# datalogger.net
KiCad netlist of a schematic drawn in Altium Designer
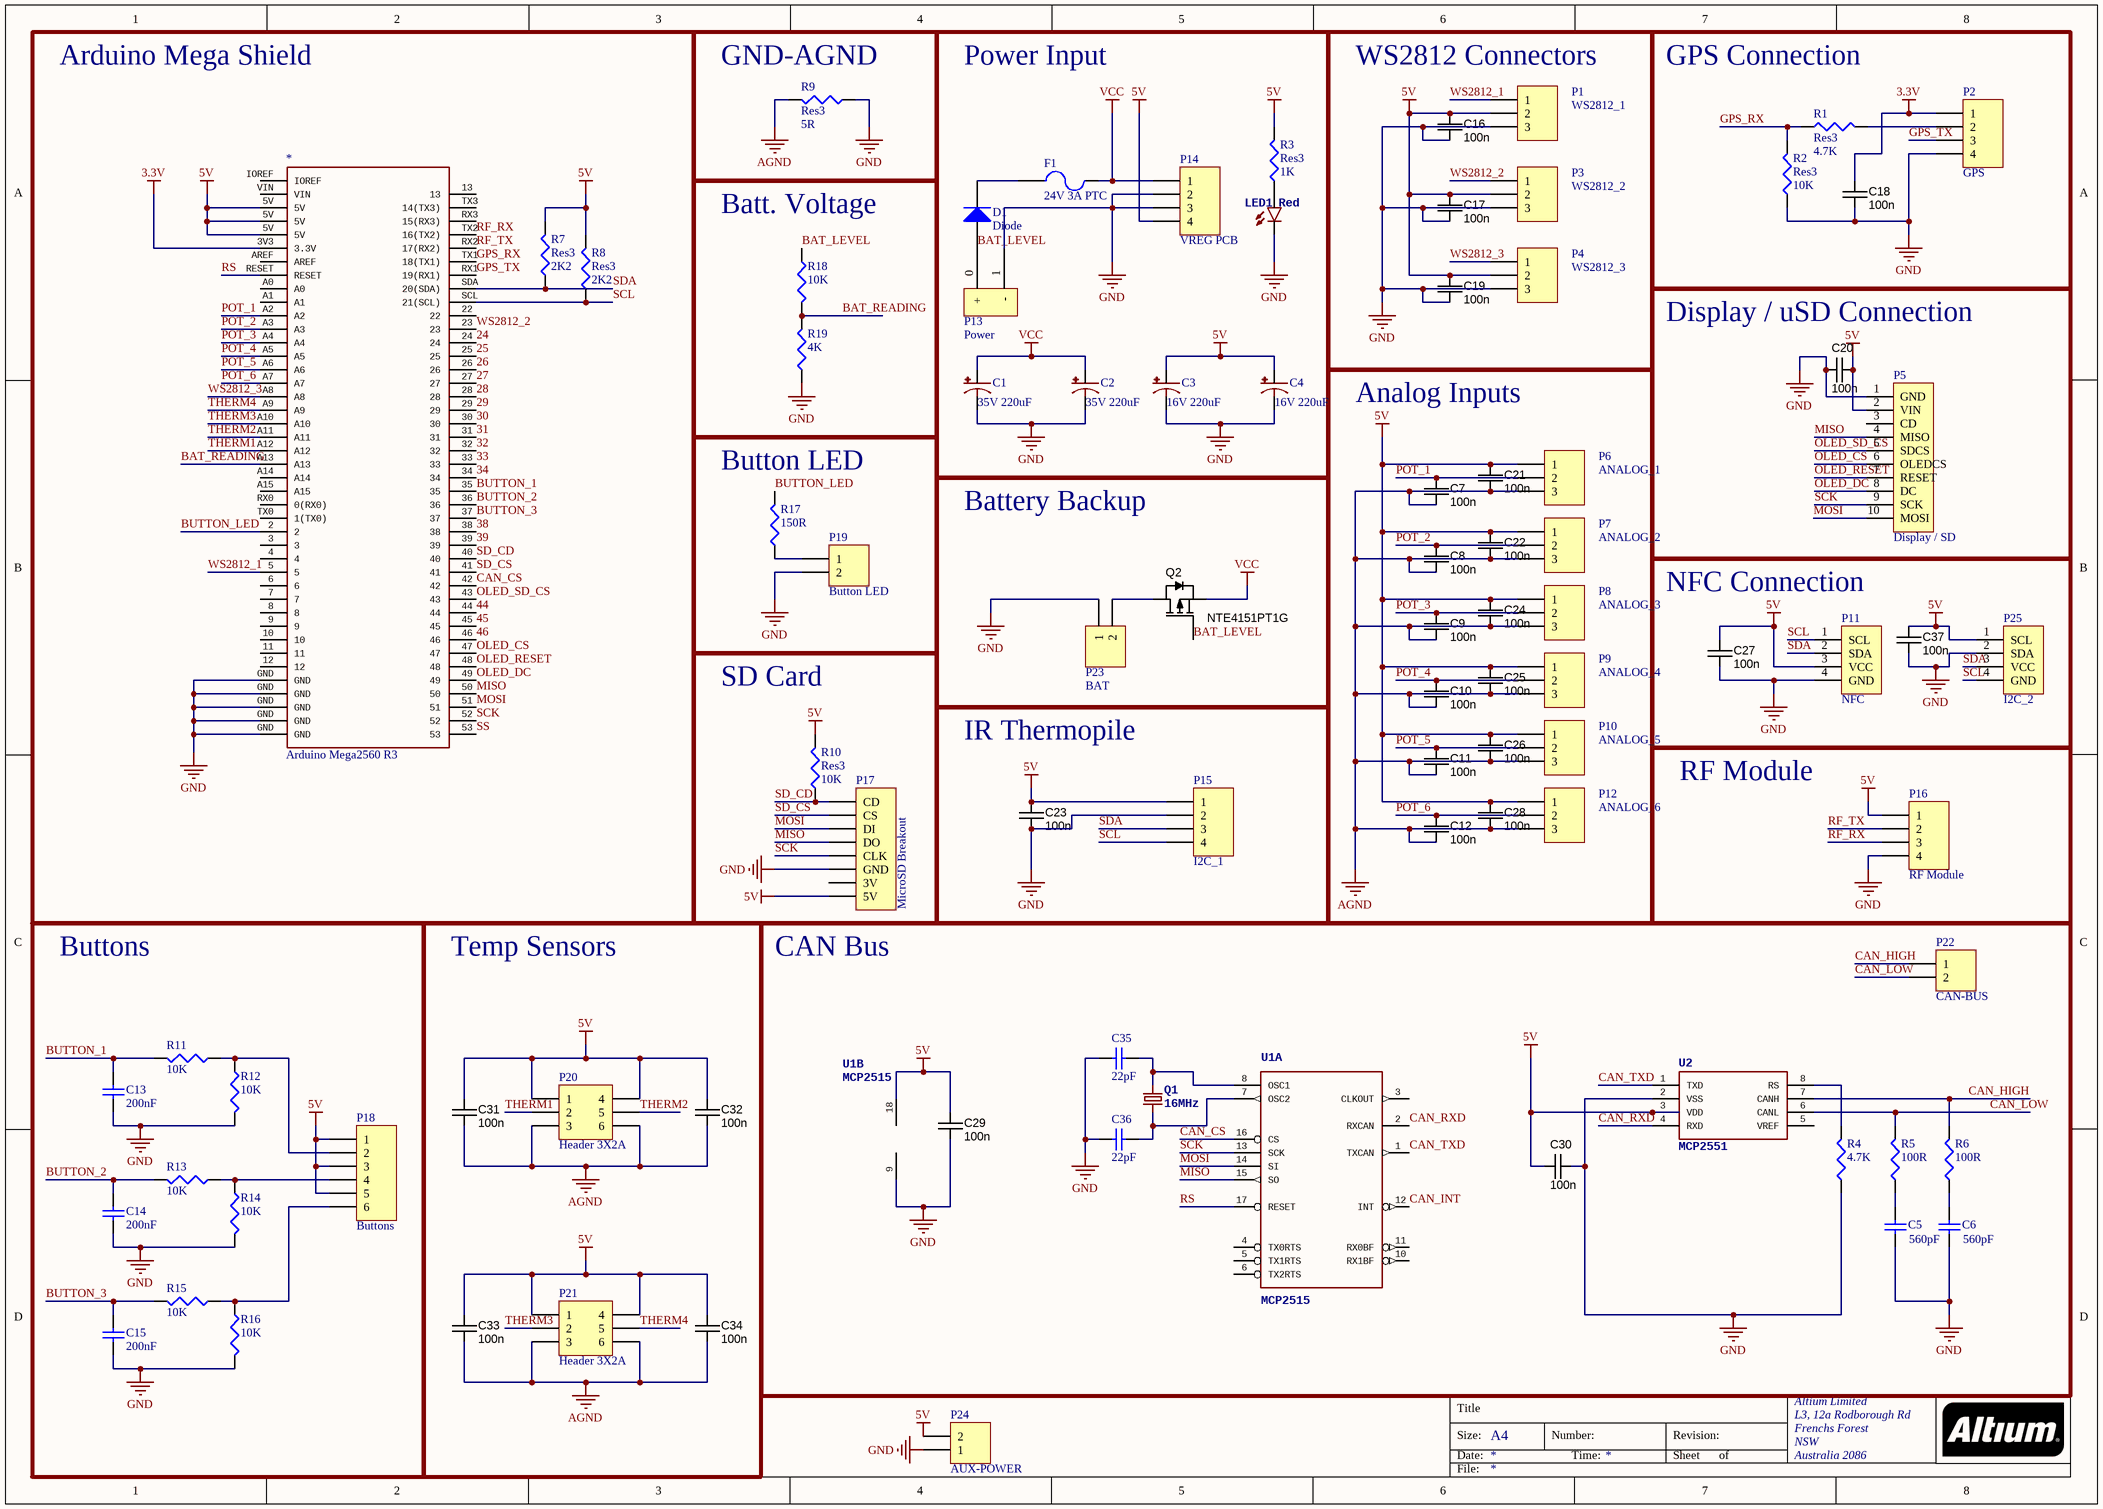
[diagram p0: datalogger.SchDoc]

(export (version "E")
  (design (tool "Eeschema 10.0.6"))
  (components
    (comp (ref "*")
      (value "Arduino Mega2560 R3")
      (footprint "Arduino Mega Shield - No Text")
      (libsource (lib "Schlib1") (part "Arduino Mega2560 R3"))
    )
    (comp (ref "C1")
      (value "35V 220uF")
      (footprint "8-DIA-CAP-3.5mm-Leads")
      (libsource (lib "Schlib1") (part "Capacitor 50V 470uF"))
    )
    (comp (ref "C2")
      (value "35V 220uF")
      (footprint "8-DIA-CAP-3.5mm-Leads")
      (libsource (lib "Schlib1") (part "Capacitor 50V 470uF"))
    )
    (comp (ref "C3")
      (value "16V 220uF")
      (footprint "6.3-DIA-CAP")
      (libsource (lib "Schlib1") (part "Capacitor 50V 470uF"))
    )
    (comp (ref "C4")
      (value "16V 220uF")
      (footprint "6.3-DIA-CAP")
      (libsource (lib "Schlib1") (part "Capacitor 50V 470uF"))
    )
    (comp (ref "C5")
      (value "560pF")
      (footprint "1608[0603]")
      (description "Capacitor (Semiconductor SIM Model)")
      (fields (field (name "Comment") "Cap Ceramic") (field (name "PUBLISHER") "Altium Limited"))
      (libsource (lib "Miscellaneous Devices") (part "Cap Semi"))
    )
    (comp (ref "C6")
      (value "560pF")
      (footprint "1608[0603]")
      (description "Capacitor (Semiconductor SIM Model)")
      (fields (field (name "Comment") "Cap Ceramic") (field (name "PUBLISHER") "Altium Limited"))
      (libsource (lib "Miscellaneous Devices") (part "Cap Semi"))
    )
    (comp (ref "C7")
      (value "100n")
      (footprint "CAPC1608X90N")
      (description "Capacitor SMD Cer 100nF 10% 50V X7R 0603")
      (fields (field (name "TOLERANCE") "±10%") (field (name "Comment") "approved sub OK"))
      (libsource (lib "PBL - Capacitors") (part "CAPC_100n_0603_X7R_50V_10%"))
    )
    (comp (ref "C8")
      (value "100n")
      (footprint "CAPC1608X90N")
      (description "Capacitor SMD Cer 100nF 10% 50V X7R 0603")
      (fields (field (name "TOLERANCE") "±10%") (field (name "Comment") "approved sub OK"))
      (libsource (lib "PBL - Capacitors") (part "CAPC_100n_0603_X7R_50V_10%"))
    )
    (comp (ref "C9")
      (value "100n")
      (footprint "CAPC1608X90N")
      (description "Capacitor SMD Cer 100nF 10% 50V X7R 0603")
      (fields (field (name "TOLERANCE") "±10%") (field (name "Comment") "approved sub OK"))
      (libsource (lib "PBL - Capacitors") (part "CAPC_100n_0603_X7R_50V_10%"))
    )
    (comp (ref "C10")
      (value "100n")
      (footprint "CAPC1608X90N")
      (description "Capacitor SMD Cer 100nF 10% 50V X7R 0603")
      (fields (field (name "TOLERANCE") "±10%") (field (name "Comment") "approved sub OK"))
      (libsource (lib "PBL - Capacitors") (part "CAPC_100n_0603_X7R_50V_10%"))
    )
    (comp (ref "C11")
      (value "100n")
      (footprint "CAPC1608X90N")
      (description "Capacitor SMD Cer 100nF 10% 50V X7R 0603")
      (fields (field (name "TOLERANCE") "±10%") (field (name "Comment") "approved sub OK"))
      (libsource (lib "PBL - Capacitors") (part "CAPC_100n_0603_X7R_50V_10%"))
    )
    (comp (ref "C12")
      (value "100n")
      (footprint "CAPC1608X90N")
      (description "Capacitor SMD Cer 100nF 10% 50V X7R 0603")
      (fields (field (name "TOLERANCE") "±10%") (field (name "Comment") "approved sub OK"))
      (libsource (lib "PBL - Capacitors") (part "CAPC_100n_0603_X7R_50V_10%"))
    )
    (comp (ref "C13")
      (value "200nF")
      (footprint "1608[0603]")
      (description "Capacitor (Semiconductor SIM Model)")
      (fields (field (name "Comment") "Cap Ceramic") (field (name "PUBLISHER") "Altium Limited"))
      (libsource (lib "Miscellaneous Devices") (part "Cap Semi"))
    )
    (comp (ref "C14")
      (value "200nF")
      (footprint "1608[0603]")
      (description "Capacitor (Semiconductor SIM Model)")
      (fields (field (name "Comment") "Cap Ceramic") (field (name "PUBLISHER") "Altium Limited"))
      (libsource (lib "Miscellaneous Devices") (part "Cap Semi"))
    )
    (comp (ref "C15")
      (value "200nF")
      (footprint "1608[0603]")
      (description "Capacitor (Semiconductor SIM Model)")
      (fields (field (name "Comment") "Cap Ceramic") (field (name "PUBLISHER") "Altium Limited"))
      (libsource (lib "Miscellaneous Devices") (part "Cap Semi"))
    )
    (comp (ref "C16")
      (value "100n")
      (footprint "CAPC1608X90N")
      (description "Capacitor SMD Cer 100nF 10% 50V X7R 0603")
      (fields (field (name "TOLERANCE") "±10%") (field (name "Comment") "approved sub OK"))
      (libsource (lib "PBL - Capacitors") (part "CAPC_100n_0603_X7R_50V_10%"))
    )
    (comp (ref "C17")
      (value "100n")
      (footprint "CAPC1608X90N")
      (description "Capacitor SMD Cer 100nF 10% 50V X7R 0603")
      (fields (field (name "TOLERANCE") "±10%") (field (name "Comment") "approved sub OK"))
      (libsource (lib "PBL - Capacitors") (part "CAPC_100n_0603_X7R_50V_10%"))
    )
    (comp (ref "C18")
      (value "100n")
      (footprint "CAPC1608X90N")
      (description "Capacitor SMD Cer 100nF 10% 50V X7R 0603")
      (fields (field (name "TOLERANCE") "±10%") (field (name "Comment") "approved sub OK"))
      (libsource (lib "PBL - Capacitors") (part "CAPC_100n_0603_X7R_50V_10%"))
    )
    (comp (ref "C19")
      (value "100n")
      (footprint "CAPC1608X90N")
      (description "Capacitor SMD Cer 100nF 10% 50V X7R 0603")
      (fields (field (name "TOLERANCE") "±10%") (field (name "Comment") "approved sub OK"))
      (libsource (lib "PBL - Capacitors") (part "CAPC_100n_0603_X7R_50V_10%"))
    )
    (comp (ref "C20")
      (value "100n")
      (footprint "CAPC1608X90N")
      (description "Capacitor SMD Cer 100nF 10% 50V X7R 0603")
      (fields (field (name "TOLERANCE") "±10%") (field (name "Comment") "approved sub OK"))
      (libsource (lib "PBL - Capacitors") (part "CAPC_100n_0603_X7R_50V_10%"))
    )
    (comp (ref "C21")
      (value "100n")
      (footprint "CAPC1608X90N")
      (description "Capacitor SMD Cer 100nF 10% 50V X7R 0603")
      (fields (field (name "TOLERANCE") "±10%") (field (name "Comment") "approved sub OK"))
      (libsource (lib "PBL - Capacitors") (part "CAPC_100n_0603_X7R_50V_10%"))
    )
    (comp (ref "C22")
      (value "100n")
      (footprint "CAPC1608X90N")
      (description "Capacitor SMD Cer 100nF 10% 50V X7R 0603")
      (fields (field (name "TOLERANCE") "±10%") (field (name "Comment") "approved sub OK"))
      (libsource (lib "PBL - Capacitors") (part "CAPC_100n_0603_X7R_50V_10%"))
    )
    (comp (ref "C23")
      (value "100n")
      (footprint "CAPC1608X90N")
      (description "Capacitor SMD Cer 100nF 10% 50V X7R 0603")
      (fields (field (name "TOLERANCE") "±10%") (field (name "Comment") "approved sub OK"))
      (libsource (lib "PBL - Capacitors") (part "CAPC_100n_0603_X7R_50V_10%"))
    )
    (comp (ref "C24")
      (value "100n")
      (footprint "CAPC1608X90N")
      (description "Capacitor SMD Cer 100nF 10% 50V X7R 0603")
      (fields (field (name "TOLERANCE") "±10%") (field (name "Comment") "approved sub OK"))
      (libsource (lib "PBL - Capacitors") (part "CAPC_100n_0603_X7R_50V_10%"))
    )
    (comp (ref "C25")
      (value "100n")
      (footprint "CAPC1608X90N")
      (description "Capacitor SMD Cer 100nF 10% 50V X7R 0603")
      (fields (field (name "TOLERANCE") "±10%") (field (name "Comment") "approved sub OK"))
      (libsource (lib "PBL - Capacitors") (part "CAPC_100n_0603_X7R_50V_10%"))
    )
    (comp (ref "C26")
      (value "100n")
      (footprint "CAPC1608X90N")
      (description "Capacitor SMD Cer 100nF 10% 50V X7R 0603")
      (fields (field (name "TOLERANCE") "±10%") (field (name "Comment") "approved sub OK"))
      (libsource (lib "PBL - Capacitors") (part "CAPC_100n_0603_X7R_50V_10%"))
    )
    (comp (ref "C27")
      (value "100n")
      (footprint "CAPC1608X90N")
      (description "Capacitor SMD Cer 100nF 10% 50V X7R 0603")
      (fields (field (name "TOLERANCE") "±10%") (field (name "Comment") "approved sub OK"))
      (libsource (lib "PBL - Capacitors") (part "CAPC_100n_0603_X7R_50V_10%"))
    )
    (comp (ref "C28")
      (value "100n")
      (footprint "CAPC1608X90N")
      (description "Capacitor SMD Cer 100nF 10% 50V X7R 0603")
      (fields (field (name "TOLERANCE") "±10%") (field (name "Comment") "approved sub OK"))
      (libsource (lib "PBL - Capacitors") (part "CAPC_100n_0603_X7R_50V_10%"))
    )
    (comp (ref "C29")
      (value "100n")
      (footprint "CAPC1608X90N")
      (description "Capacitor SMD Cer 100nF 10% 50V X7R 0603")
      (fields (field (name "TOLERANCE") "±10%") (field (name "Comment") "approved sub OK"))
      (libsource (lib "PBL - Capacitors") (part "CAPC_100n_0603_X7R_50V_10%"))
    )
    (comp (ref "C30")
      (value "100n")
      (footprint "CAPC1608X90N")
      (description "Capacitor SMD Cer 100nF 10% 50V X7R 0603")
      (fields (field (name "TOLERANCE") "±10%") (field (name "Comment") "approved sub OK"))
      (libsource (lib "PBL - Capacitors") (part "CAPC_100n_0603_X7R_50V_10%"))
    )
    (comp (ref "C31")
      (value "100n")
      (footprint "CAPC1608X90N")
      (description "Capacitor SMD Cer 100nF 10% 50V X7R 0603")
      (fields (field (name "TOLERANCE") "±10%") (field (name "Comment") "approved sub OK"))
      (libsource (lib "PBL - Capacitors") (part "CAPC_100n_0603_X7R_50V_10%"))
    )
    (comp (ref "C32")
      (value "100n")
      (footprint "CAPC1608X90N")
      (description "Capacitor SMD Cer 100nF 10% 50V X7R 0603")
      (fields (field (name "TOLERANCE") "±10%") (field (name "Comment") "approved sub OK"))
      (libsource (lib "PBL - Capacitors") (part "CAPC_100n_0603_X7R_50V_10%"))
    )
    (comp (ref "C33")
      (value "100n")
      (footprint "CAPC1608X90N")
      (description "Capacitor SMD Cer 100nF 10% 50V X7R 0603")
      (fields (field (name "TOLERANCE") "±10%") (field (name "Comment") "approved sub OK"))
      (libsource (lib "PBL - Capacitors") (part "CAPC_100n_0603_X7R_50V_10%"))
    )
    (comp (ref "C34")
      (value "100n")
      (footprint "CAPC1608X90N")
      (description "Capacitor SMD Cer 100nF 10% 50V X7R 0603")
      (fields (field (name "TOLERANCE") "±10%") (field (name "Comment") "approved sub OK"))
      (libsource (lib "PBL - Capacitors") (part "CAPC_100n_0603_X7R_50V_10%"))
    )
    (comp (ref "C35")
      (value "22pF")
      (footprint "1608[0603]")
      (description "Capacitor (Semiconductor SIM Model)")
      (fields (field (name "Comment") "Cap Ceramic") (field (name "PUBLISHER") "Altium Limited"))
      (libsource (lib "Miscellaneous Devices") (part "Cap Semi"))
    )
    (comp (ref "C36")
      (value "22pF")
      (footprint "1608[0603]")
      (description "Capacitor (Semiconductor SIM Model)")
      (fields (field (name "Comment") "Cap Ceramic") (field (name "PUBLISHER") "Altium Limited"))
      (libsource (lib "Miscellaneous Devices") (part "Cap Semi"))
    )
    (comp (ref "C37")
      (value "100n")
      (footprint "CAPC1608X90N")
      (description "Capacitor SMD Cer 100nF 10% 50V X7R 0603")
      (fields (field (name "TOLERANCE") "±10%") (field (name "Comment") "approved sub OK"))
      (libsource (lib "PBL - Capacitors") (part "CAPC_100n_0603_X7R_50V_10%"))
    )
    (comp (ref "D1")
      (value "Diode")
      (footprint "SMC")
      (description "Default Diode")
      (fields (field (name "PUBLISHER") "Altium Limited"))
      (libsource (lib "Miscellaneous Devices") (part "Diode"))
    )
    (comp (ref "F1")
      (value "24V 3A PTC")
      (footprint "MF-LSMF SMD PTC Fuse")
      (description "Fuse")
      (fields (field (name "PUBLISHER") "Altium Limited"))
      (libsource (lib "Miscellaneous Devices") (part "Fuse 2"))
    )
    (comp (ref "LED1")
      (value "Red")
      (footprint "LED-0603")
      (description "Power Indicator")
      (libsource (lib "SparkFun-LED") (part "LED0603"))
    )
    (comp (ref "P1")
      (value "WS2812_1")
      (footprint "HDR1X3")
      (description "Header, 3-Pin")
      (fields (field (name "PUBLISHER") "Altium Limited"))
      (libsource (lib "Miscellaneous Connectors") (part "Header 3"))
    )
    (comp (ref "P2")
      (value "GPS")
      (footprint "HDR1X4")
      (description "Header, 4-Pin")
      (fields (field (name "PUBLISHER") "Altium Limited"))
      (libsource (lib "Miscellaneous Connectors") (part "Header 4"))
    )
    (comp (ref "P3")
      (value "WS2812_2")
      (footprint "HDR1X3")
      (description "Header, 3-Pin")
      (fields (field (name "PUBLISHER") "Altium Limited"))
      (libsource (lib "Miscellaneous Connectors") (part "Header 3"))
    )
    (comp (ref "P4")
      (value "WS2812_3")
      (footprint "HDR1X3")
      (description "Header, 3-Pin")
      (fields (field (name "PUBLISHER") "Altium Limited"))
      (libsource (lib "Miscellaneous Connectors") (part "Header 3"))
    )
    (comp (ref "P5")
      (value "Display / SD")
      (footprint "HDR1X10")
      (description "Header, 10-Pin")
      (fields (field (name "PUBLISHER") "Altium Limited"))
      (libsource (lib "Miscellaneous Connectors") (part "Header 10"))
    )
    (comp (ref "P6")
      (value "ANALOG_1")
      (footprint "HDR1X3")
      (description "Header, 3-Pin")
      (fields (field (name "PUBLISHER") "Altium Limited"))
      (libsource (lib "Miscellaneous Connectors") (part "Header 3"))
    )
    (comp (ref "P7")
      (value "ANALOG_2")
      (footprint "HDR1X3")
      (description "Header, 3-Pin")
      (fields (field (name "PUBLISHER") "Altium Limited"))
      (libsource (lib "Miscellaneous Connectors") (part "Header 3"))
    )
    (comp (ref "P8")
      (value "ANALOG_3")
      (footprint "HDR1X3")
      (description "Header, 3-Pin")
      (fields (field (name "PUBLISHER") "Altium Limited"))
      (libsource (lib "Miscellaneous Connectors") (part "Header 3"))
    )
    (comp (ref "P9")
      (value "ANALOG_4")
      (footprint "HDR1X3")
      (description "Header, 3-Pin")
      (fields (field (name "PUBLISHER") "Altium Limited"))
      (libsource (lib "Miscellaneous Connectors") (part "Header 3"))
    )
    (comp (ref "P10")
      (value "ANALOG_5")
      (footprint "HDR1X3")
      (description "Header, 3-Pin")
      (fields (field (name "PUBLISHER") "Altium Limited"))
      (libsource (lib "Miscellaneous Connectors") (part "Header 3"))
    )
    (comp (ref "P11")
      (value "NFC")
      (footprint "HDR1X4")
      (description "Header, 4-Pin")
      (fields (field (name "PUBLISHER") "Altium Limited"))
      (libsource (lib "") (part "Header 4_1"))
    )
    (comp (ref "P12")
      (value "ANALOG_6")
      (footprint "HDR1X3")
      (description "Header, 3-Pin")
      (fields (field (name "PUBLISHER") "Altium Limited"))
      (libsource (lib "Miscellaneous Connectors") (part "Header 3"))
    )
    (comp (ref "P13")
      (value "Power")
      (footprint "2P 5.08mm Screw Terminal")
      (libsource (lib "Schlib1") (part "2P Screw Terminal 5.08mm"))
    )
    (comp (ref "P14")
      (value "VREG PCB")
      (footprint "HDR1X4")
      (description "Header, 4-Pin")
      (fields (field (name "PUBLISHER") "Altium Limited"))
      (libsource (lib "Miscellaneous Connectors") (part "Header 4"))
    )
    (comp (ref "P15")
      (value "I2C_1")
      (footprint "HDR1X4")
      (description "Header, 4-Pin")
      (fields (field (name "PUBLISHER") "Altium Limited"))
      (libsource (lib "Miscellaneous Connectors") (part "Header 4"))
    )
    (comp (ref "P16")
      (value "RF Module")
      (footprint "HDR1X4")
      (description "Header, 4-Pin")
      (fields (field (name "PUBLISHER") "Altium Limited"))
      (libsource (lib "Miscellaneous Connectors") (part "Header 4"))
    )
    (comp (ref "P17")
      (value "MicroSD Breakout")
      (footprint "HDR1X8")
      (description "Header, 8-Pin")
      (fields (field (name "PUBLISHER") "Altium Limited"))
      (libsource (lib "Miscellaneous Connectors") (part "Header 8"))
    )
    (comp (ref "P18")
      (value "Buttons")
      (footprint "HDR1X6")
      (description "Header, 6-Pin")
      (fields (field (name "PUBLISHER") "Altium Limited"))
      (libsource (lib "Miscellaneous Connectors") (part "Header 6"))
    )
    (comp (ref "P19")
      (value "Button LED")
      (footprint "HDR1X2")
      (description "Header, 2-Pin")
      (fields (field (name "PUBLISHER") "Altium Limited"))
      (libsource (lib "Miscellaneous Connectors") (part "Header 2"))
    )
    (comp (ref "P20")
      (value "Header 3X2A")
      (footprint "HDR2X3_CEN")
      (description "Header, 3-Pin, Dual row")
      (fields (field (name "PUBLISHER") "Altium Limited"))
      (libsource (lib "Miscellaneous Connectors") (part "Header 3X2A"))
    )
    (comp (ref "P21")
      (value "Header 3X2A")
      (footprint "HDR2X3_CEN")
      (description "Header, 3-Pin, Dual row")
      (fields (field (name "PUBLISHER") "Altium Limited"))
      (libsource (lib "Miscellaneous Connectors") (part "Header 3X2A"))
    )
    (comp (ref "P22")
      (value "CAN-BUS")
      (footprint "HDR1X2")
      (description "Header, 2-Pin")
      (fields (field (name "PUBLISHER") "Altium Limited"))
      (libsource (lib "Miscellaneous Connectors") (part "Header 2"))
    )
    (comp (ref "P23")
      (value "BAT")
      (footprint "HDR1X2")
      (description "Header, 2-Pin")
      (fields (field (name "PUBLISHER") "Altium Limited"))
      (libsource (lib "") (part "Header 2_2"))
    )
    (comp (ref "P24")
      (value "AUX-POWER")
      (footprint "HDR1X2")
      (description "Header, 2-Pin")
      (fields (field (name "PUBLISHER") "Altium Limited"))
      (libsource (lib "") (part "Header 2_1"))
    )
    (comp (ref "P25")
      (value "I2C_2")
      (footprint "HDR1X4")
      (description "Header, 4-Pin")
      (fields (field (name "PUBLISHER") "Altium Limited"))
      (libsource (lib "") (part "Header 4_1"))
    )
    (comp (ref "Q1")
      (value "16MHz")
      (footprint "HC-46X")
      (libsource (lib "SparkFun-FreqCtrl") (part "CRYSTALHC49US"))
    )
    (comp (ref "Q2")
      (value "P-Channel")
      (footprint "SOT23-3")
      (description "MOSFET SMD P-CH 20V 0.76A 0.313W SOT523F")
      (fields (field (name "MANUFACTURER PART NUMBER 1") "NTE4151PT1G"))
      (libsource (lib "PBL - Transistors") (part "MOSFET_P-CH_NTE4151PT1G"))
    )
    (comp (ref "R1")
      (value "Res3")
      (footprint "J1-0603")
      (description "Resistor")
      (fields (field (name "ALTIUM_VALUE") "4.7K") (field (name "PUBLISHER") "Altium Limited"))
      (libsource (lib "Miscellaneous Devices") (part "Res3"))
    )
    (comp (ref "R2")
      (value "Res3")
      (footprint "J1-0603")
      (description "Resistor")
      (fields (field (name "ALTIUM_VALUE") "10K") (field (name "PUBLISHER") "Altium Limited"))
      (libsource (lib "Miscellaneous Devices") (part "Res3"))
    )
    (comp (ref "R3")
      (value "Res3")
      (footprint "J1-0603")
      (description "Resistor")
      (fields (field (name "ALTIUM_VALUE") "1K") (field (name "PUBLISHER") "Altium Limited"))
      (libsource (lib "Miscellaneous Devices") (part "Res3"))
    )
    (comp (ref "R4")
      (value "4.7K")
      (footprint "J1-0603")
      (description "Resistor")
      (fields (field (name "PUBLISHER") "Altium Limited"))
      (libsource (lib "Miscellaneous Devices") (part "Res3"))
    )
    (comp (ref "R5")
      (value "100R")
      (footprint "J1-0603")
      (description "Resistor")
      (fields (field (name "PUBLISHER") "Altium Limited"))
      (libsource (lib "Miscellaneous Devices") (part "Res3"))
    )
    (comp (ref "R6")
      (value "100R")
      (footprint "J1-0603")
      (description "Resistor")
      (fields (field (name "PUBLISHER") "Altium Limited"))
      (libsource (lib "Miscellaneous Devices") (part "Res3"))
    )
    (comp (ref "R7")
      (value "Res3")
      (footprint "J1-0603")
      (description "Resistor")
      (fields (field (name "ALTIUM_VALUE") "2K2") (field (name "PUBLISHER") "Altium Limited"))
      (libsource (lib "Miscellaneous Devices") (part "Res3"))
    )
    (comp (ref "R8")
      (value "Res3")
      (footprint "J1-0603")
      (description "Resistor")
      (fields (field (name "ALTIUM_VALUE") "2K2") (field (name "PUBLISHER") "Altium Limited"))
      (libsource (lib "Miscellaneous Devices") (part "Res3"))
    )
    (comp (ref "R9")
      (value "Res3")
      (footprint "0805")
      (description "Resistor")
      (fields (field (name "ALTIUM_VALUE") "5R") (field (name "PUBLISHER") "Altium Limited"))
      (libsource (lib "Miscellaneous Devices") (part "Res3"))
    )
    (comp (ref "R10")
      (value "Res3")
      (footprint "J1-0603")
      (description "Resistor")
      (fields (field (name "ALTIUM_VALUE") "10K") (field (name "PUBLISHER") "Altium Limited"))
      (libsource (lib "Miscellaneous Devices") (part "Res3"))
    )
    (comp (ref "R11")
      (value "10K")
      (footprint "J1-0603")
      (description "Resistor")
      (fields (field (name "PUBLISHER") "Altium Limited"))
      (libsource (lib "Miscellaneous Devices") (part "Res3"))
    )
    (comp (ref "R12")
      (value "10K")
      (footprint "J1-0603")
      (description "Resistor")
      (fields (field (name "PUBLISHER") "Altium Limited"))
      (libsource (lib "Miscellaneous Devices") (part "Res3"))
    )
    (comp (ref "R13")
      (value "10K")
      (footprint "J1-0603")
      (description "Resistor")
      (fields (field (name "PUBLISHER") "Altium Limited"))
      (libsource (lib "Miscellaneous Devices") (part "Res3"))
    )
    (comp (ref "R14")
      (value "10K")
      (footprint "J1-0603")
      (description "Resistor")
      (fields (field (name "PUBLISHER") "Altium Limited"))
      (libsource (lib "Miscellaneous Devices") (part "Res3"))
    )
    (comp (ref "R15")
      (value "10K")
      (footprint "J1-0603")
      (description "Resistor")
      (fields (field (name "PUBLISHER") "Altium Limited"))
      (libsource (lib "Miscellaneous Devices") (part "Res3"))
    )
    (comp (ref "R16")
      (value "10K")
      (footprint "J1-0603")
      (description "Resistor")
      (fields (field (name "PUBLISHER") "Altium Limited"))
      (libsource (lib "Miscellaneous Devices") (part "Res3"))
    )
    (comp (ref "R17")
      (value "150R")
      (footprint "J1-0603")
      (description "Resistor")
      (fields (field (name "PUBLISHER") "Altium Limited"))
      (libsource (lib "Miscellaneous Devices") (part "Res3"))
    )
    (comp (ref "R18")
      (value "10K")
      (footprint "J1-0603")
      (description "Resistor")
      (fields (field (name "PUBLISHER") "Altium Limited"))
      (libsource (lib "Miscellaneous Devices") (part "Res3"))
    )
    (comp (ref "R19")
      (value "4K")
      (footprint "J1-0603")
      (description "Resistor")
      (fields (field (name "PUBLISHER") "Altium Limited"))
      (libsource (lib "Miscellaneous Devices") (part "Res3"))
    )
    (comp (ref "U1")
      (value "MCP2515")
      (footprint "SO-18W")
      (libsource (lib "CAN-Bus_Shield") (part "MCP2510SO"))
    )
    (comp (ref "U2")
      (value "MCP2551")
      (footprint "SO08")
      (libsource (lib "SparkFun-DigitalIC") (part "MCP2551"))
    )
  )
  (nets
    (net (code "1") (name "/24") (class "Default")
      (node (ref "*") (pin "24") (pinfunction "24_24") (pintype "passive"))
    )
    (net (code "2") (name "/25") (class "Default")
      (node (ref "*") (pin "25") (pinfunction "25_25") (pintype "passive"))
    )
    (net (code "3") (name "/26") (class "Default")
      (node (ref "*") (pin "26") (pinfunction "26_26") (pintype "passive"))
    )
    (net (code "4") (name "/27") (class "Default")
      (node (ref "*") (pin "27") (pinfunction "27_27") (pintype "passive"))
    )
    (net (code "5") (name "/28") (class "Default")
      (node (ref "*") (pin "28") (pinfunction "28_28") (pintype "passive"))
    )
    (net (code "6") (name "/29") (class "Default")
      (node (ref "*") (pin "29") (pinfunction "29_29") (pintype "passive"))
    )
    (net (code "7") (name "/30") (class "Default")
      (node (ref "*") (pin "30") (pinfunction "30_30") (pintype "passive"))
    )
    (net (code "8") (name "/31") (class "Default")
      (node (ref "*") (pin "31") (pinfunction "31_31") (pintype "passive"))
    )
    (net (code "9") (name "/32") (class "Default")
      (node (ref "*") (pin "32") (pinfunction "32_32") (pintype "passive"))
    )
    (net (code "10") (name "/33") (class "Default")
      (node (ref "*") (pin "33") (pinfunction "33_33") (pintype "passive"))
    )
    (net (code "11") (name "/34") (class "Default")
      (node (ref "*") (pin "34") (pinfunction "34_34") (pintype "passive"))
    )
    (net (code "12") (name "/38") (class "Default")
      (node (ref "*") (pin "38") (pinfunction "38_38") (pintype "passive"))
    )
    (net (code "13") (name "/39") (class "Default")
      (node (ref "*") (pin "39") (pinfunction "39_39") (pintype "passive"))
    )
    (net (code "14") (name "/44") (class "Default")
      (node (ref "*") (pin "44") (pinfunction "44_44") (pintype "passive"))
    )
    (net (code "15") (name "/45") (class "Default")
      (node (ref "*") (pin "45") (pinfunction "45_45") (pintype "passive"))
    )
    (net (code "16") (name "/46") (class "Default")
      (node (ref "*") (pin "46") (pinfunction "46_46") (pintype "passive"))
    )
    (net (code "17") (name "/BAT_LEVEL") (class "Default")
      (node (ref "D1") (pin "1") (pinfunction "A_1") (pintype "passive"))
      (node (ref "P13") (pin "0") (pinfunction "+_0") (pintype "passive"))
      (node (ref "Q2") (pin "1") (pinfunction "G_1") (pintype "passive"))
      (node (ref "R18") (pin "1") (pinfunction "1_1") (pintype "passive"))
    )
    (net (code "18") (name "/BAT_READING") (class "Default")
      (node (ref "*") (pin "A13") (pinfunction "A13_A13") (pintype "passive"))
      (node (ref "R18") (pin "2") (pinfunction "2_2") (pintype "passive"))
      (node (ref "R19") (pin "2") (pinfunction "2_2") (pintype "passive"))
    )
    (net (code "19") (name "/BUTTON_1") (class "Default")
      (node (ref "*") (pin "35") (pinfunction "35_35") (pintype "passive"))
      (node (ref "C13") (pin "1") (pinfunction "1_1") (pintype "passive"))
      (node (ref "R11") (pin "2") (pinfunction "2_2") (pintype "passive"))
    )
    (net (code "20") (name "/BUTTON_2") (class "Default")
      (node (ref "*") (pin "36") (pinfunction "36_36") (pintype "passive"))
      (node (ref "C14") (pin "1") (pinfunction "1_1") (pintype "passive"))
      (node (ref "R13") (pin "2") (pinfunction "2_2") (pintype "passive"))
    )
    (net (code "21") (name "/BUTTON_3") (class "Default")
      (node (ref "*") (pin "37") (pinfunction "37_37") (pintype "passive"))
      (node (ref "C15") (pin "1") (pinfunction "1_1") (pintype "passive"))
      (node (ref "R15") (pin "2") (pinfunction "2_2") (pintype "passive"))
    )
    (net (code "22") (name "/BUTTON_LED") (class "Default")
      (node (ref "*") (pin "2") (pinfunction "2_2") (pintype "passive"))
      (node (ref "R17") (pin "2") (pinfunction "2_2") (pintype "passive"))
    )
    (net (code "23") (name "/CAN_CS") (class "Default")
      (node (ref "*") (pin "42") (pinfunction "42_42") (pintype "passive"))
      (node (ref "U1") (pin "16") (pinfunction "CS_16") (pintype "passive"))
    )
    (net (code "24") (name "/CAN_HIGH") (class "Default")
      (node (ref "P22") (pin "1") (pinfunction "1_1") (pintype "passive"))
      (node (ref "R6") (pin "2") (pinfunction "2_2") (pintype "passive"))
      (node (ref "U2") (pin "7") (pinfunction "CANH_7") (pintype "passive"))
    )
    (net (code "25") (name "/CAN_INT") (class "Default")
      (node (ref "U1") (pin "12") (pinfunction "INT_12") (pintype "output"))
    )
    (net (code "26") (name "/CAN_LOW") (class "Default")
      (node (ref "P22") (pin "2") (pinfunction "2_2") (pintype "passive"))
      (node (ref "R5") (pin "2") (pinfunction "2_2") (pintype "passive"))
      (node (ref "U2") (pin "6") (pinfunction "CANL_6") (pintype "passive"))
    )
    (net (code "27") (name "/CAN_RXD") (class "Default")
      (node (ref "U1") (pin "2") (pinfunction "RXCAN_2") (pintype "passive"))
      (node (ref "U2") (pin "4") (pinfunction "RXD_4") (pintype "passive"))
    )
    (net (code "28") (name "/CAN_TXD") (class "Default")
      (node (ref "U1") (pin "1") (pinfunction "TXCAN_1") (pintype "output"))
      (node (ref "U2") (pin "1") (pinfunction "TXD_1") (pintype "passive"))
    )
    (net (code "29") (name "/GPS_RX") (class "Default")
      (node (ref "*") (pin "TX1") (pinfunction "18(TX1)_TX1") (pintype "passive"))
      (node (ref "R1") (pin "1") (pinfunction "1_1") (pintype "passive"))
      (node (ref "R2") (pin "2") (pinfunction "2_2") (pintype "passive"))
    )
    (net (code "30") (name "/GPS_TX") (class "Default")
      (node (ref "*") (pin "RX1") (pinfunction "19(RX1)_RX1") (pintype "passive"))
      (node (ref "P2") (pin "3") (pinfunction "3_3") (pintype "passive"))
    )
    (net (code "31") (name "/MISO") (class "Default")
      (node (ref "*") (pin "50") (pinfunction "50_50") (pintype "passive"))
      (node (ref "P17") (pin "4") (pinfunction "DO_4") (pintype "passive"))
      (node (ref "P5") (pin "4") (pinfunction "MISO_4") (pintype "passive"))
      (node (ref "U1") (pin "15") (pinfunction "SO_15") (pintype "output"))
    )
    (net (code "32") (name "/MOSI") (class "Default")
      (node (ref "*") (pin "51") (pinfunction "51_51") (pintype "passive"))
      (node (ref "P17") (pin "3") (pinfunction "DI_3") (pintype "passive"))
      (node (ref "P5") (pin "10") (pinfunction "MOSI_10") (pintype "passive"))
      (node (ref "U1") (pin "14") (pinfunction "SI_14") (pintype "passive"))
    )
    (net (code "33") (name "/OLED_CS") (class "Default")
      (node (ref "*") (pin "47") (pinfunction "47_47") (pintype "passive"))
      (node (ref "P5") (pin "6") (pinfunction "OLEDCS_6") (pintype "passive"))
    )
    (net (code "34") (name "/OLED_DC") (class "Default")
      (node (ref "*") (pin "49") (pinfunction "49_49") (pintype "passive"))
      (node (ref "P5") (pin "8") (pinfunction "DC_8") (pintype "passive"))
    )
    (net (code "35") (name "/OLED_RESET") (class "Default")
      (node (ref "*") (pin "48") (pinfunction "48_48") (pintype "passive"))
      (node (ref "P5") (pin "7") (pinfunction "RESET_7") (pintype "passive"))
    )
    (net (code "36") (name "/OLED_SD_CS") (class "Default")
      (node (ref "*") (pin "43") (pinfunction "43_43") (pintype "passive"))
      (node (ref "P5") (pin "5") (pinfunction "SDCS_5") (pintype "passive"))
    )
    (net (code "37") (name "/POT_1") (class "Default")
      (node (ref "*") (pin "A2") (pinfunction "A2_A2") (pintype "passive"))
      (node (ref "C7") (pin "1") (pintype "passive"))
      (node (ref "P6") (pin "2") (pinfunction "2_2") (pintype "passive"))
    )
    (net (code "38") (name "/POT_2") (class "Default")
      (node (ref "*") (pin "A3") (pinfunction "A3_A3") (pintype "passive"))
      (node (ref "C8") (pin "1") (pintype "passive"))
      (node (ref "P7") (pin "2") (pinfunction "2_2") (pintype "passive"))
    )
    (net (code "39") (name "/POT_3") (class "Default")
      (node (ref "*") (pin "A4") (pinfunction "A4_A4") (pintype "passive"))
      (node (ref "C9") (pin "1") (pintype "passive"))
      (node (ref "P8") (pin "2") (pinfunction "2_2") (pintype "passive"))
    )
    (net (code "40") (name "/POT_4") (class "Default")
      (node (ref "*") (pin "A5") (pinfunction "A5_A5") (pintype "passive"))
      (node (ref "C10") (pin "1") (pintype "passive"))
      (node (ref "P9") (pin "2") (pinfunction "2_2") (pintype "passive"))
    )
    (net (code "41") (name "/POT_5") (class "Default")
      (node (ref "*") (pin "A6") (pinfunction "A6_A6") (pintype "passive"))
      (node (ref "C11") (pin "1") (pintype "passive"))
      (node (ref "P10") (pin "2") (pinfunction "2_2") (pintype "passive"))
    )
    (net (code "42") (name "/POT_6") (class "Default")
      (node (ref "*") (pin "A7") (pinfunction "A7_A7") (pintype "passive"))
      (node (ref "C12") (pin "1") (pintype "passive"))
      (node (ref "P12") (pin "2") (pinfunction "2_2") (pintype "passive"))
    )
    (net (code "43") (name "/RF_RX") (class "Default")
      (node (ref "*") (pin "TX2") (pinfunction "16(TX2)_TX2") (pintype "passive"))
      (node (ref "P16") (pin "3") (pinfunction "3_3") (pintype "passive"))
    )
    (net (code "44") (name "/RF_TX") (class "Default")
      (node (ref "*") (pin "RX2") (pinfunction "17(RX2)_RX2") (pintype "passive"))
      (node (ref "P16") (pin "2") (pinfunction "2_2") (pintype "passive"))
    )
    (net (code "45") (name "/RS") (class "Default")
      (node (ref "*") (pin "RESET") (pinfunction "RESET_RESET") (pintype "passive"))
      (node (ref "U1") (pin "17") (pinfunction "RESET_17") (pintype "passive"))
    )
    (net (code "46") (name "/SCK") (class "Default")
      (node (ref "*") (pin "52") (pinfunction "52_52") (pintype "passive"))
      (node (ref "P17") (pin "5") (pinfunction "CLK_5") (pintype "passive"))
      (node (ref "P5") (pin "9") (pinfunction "SCK_9") (pintype "passive"))
      (node (ref "U1") (pin "13") (pinfunction "SCK_13") (pintype "passive"))
    )
    (net (code "47") (name "/SCL") (class "Default")
      (node (ref "*") (pin "SCL") (pinfunction "21(SCL)_SCL") (pintype "passive"))
      (node (ref "P11") (pin "1") (pinfunction "SCL_1") (pintype "passive"))
      (node (ref "P15") (pin "4") (pinfunction "4_4") (pintype "passive"))
      (node (ref "P25") (pin "4") (pinfunction "GND_4") (pintype "passive"))
      (node (ref "R8") (pin "1") (pinfunction "1_1") (pintype "passive"))
    )
    (net (code "48") (name "/SDA") (class "Default")
      (node (ref "*") (pin "SDA") (pinfunction "20(SDA)_SDA") (pintype "passive"))
      (node (ref "P11") (pin "2") (pinfunction "SDA_2") (pintype "passive"))
      (node (ref "P15") (pin "3") (pinfunction "3_3") (pintype "passive"))
      (node (ref "P25") (pin "3") (pinfunction "VCC_3") (pintype "passive"))
      (node (ref "R7") (pin "1") (pinfunction "1_1") (pintype "passive"))
    )
    (net (code "49") (name "/SD_CD") (class "Default")
      (node (ref "*") (pin "40") (pinfunction "40_40") (pintype "passive"))
      (node (ref "P17") (pin "1") (pinfunction "CD_1") (pintype "passive"))
      (node (ref "R10") (pin "1") (pinfunction "1_1") (pintype "passive"))
    )
    (net (code "50") (name "/SD_CS") (class "Default")
      (node (ref "*") (pin "41") (pinfunction "41_41") (pintype "passive"))
      (node (ref "P17") (pin "2") (pinfunction "CS_2") (pintype "passive"))
    )
    (net (code "51") (name "/SS") (class "Default")
      (node (ref "*") (pin "53") (pinfunction "53_53") (pintype "passive"))
    )
    (net (code "52") (name "/THERM1") (class "Default")
      (node (ref "*") (pin "A12") (pinfunction "A12_A12") (pintype "passive"))
      (node (ref "P20") (pin "2") (pinfunction "2_2") (pintype "passive"))
    )
    (net (code "53") (name "/THERM2") (class "Default")
      (node (ref "*") (pin "A11") (pinfunction "A11_A11") (pintype "passive"))
      (node (ref "P20") (pin "5") (pinfunction "5_5") (pintype "passive"))
    )
    (net (code "54") (name "/THERM3") (class "Default")
      (node (ref "*") (pin "A10") (pinfunction "A10_A10") (pintype "passive"))
      (node (ref "P21") (pin "2") (pinfunction "2_2") (pintype "passive"))
    )
    (net (code "55") (name "/THERM4") (class "Default")
      (node (ref "*") (pin "A9") (pinfunction "A9_A9") (pintype "passive"))
      (node (ref "P21") (pin "5") (pinfunction "5_5") (pintype "passive"))
    )
    (net (code "56") (name "/WS2812_1") (class "Default")
      (node (ref "*") (pin "5") (pinfunction "5_5") (pintype "passive"))
      (node (ref "P1") (pin "1") (pinfunction "1_1") (pintype "passive"))
    )
    (net (code "57") (name "/WS2812_2") (class "Default")
      (node (ref "*") (pin "23") (pinfunction "23_23") (pintype "passive"))
      (node (ref "P3") (pin "1") (pinfunction "1_1") (pintype "passive"))
    )
    (net (code "58") (name "/WS2812_3") (class "Default")
      (node (ref "*") (pin "A8") (pinfunction "A8_A8") (pintype "passive"))
      (node (ref "P4") (pin "1") (pinfunction "1_1") (pintype "passive"))
    )
    (net (code "59") (name "3.3V") (class "Default")
      (node (ref "*") (pin "3V3") (pinfunction "3.3V_3V3") (pintype "passive"))
      (node (ref "C18") (pin "1") (pintype "passive"))
      (node (ref "P2") (pin "1") (pinfunction "1_1") (pintype "passive"))
    )
    (net (code "60") (name "5V") (class "Default")
      (node (ref "*") (pin "5V") (pinfunction "5V_5V") (pintype "passive"))
      (node (ref "C16") (pin "1") (pintype "passive"))
      (node (ref "C17") (pin "1") (pintype "passive"))
      (node (ref "C19") (pin "1") (pintype "passive"))
      (node (ref "C20") (pin "2") (pintype "passive"))
      (node (ref "C21") (pin "1") (pintype "passive"))
      (node (ref "C22") (pin "1") (pintype "passive"))
      (node (ref "C23") (pin "1") (pintype "passive"))
      (node (ref "C24") (pin "1") (pintype "passive"))
      (node (ref "C25") (pin "1") (pintype "passive"))
      (node (ref "C26") (pin "1") (pintype "passive"))
      (node (ref "C27") (pin "2") (pintype "passive"))
      (node (ref "C28") (pin "1") (pintype "passive"))
      (node (ref "C29") (pin "1") (pintype "passive"))
      (node (ref "C3") (pin "2") (pinfunction "+_2") (pintype "passive"))
      (node (ref "C30") (pin "2") (pintype "passive"))
      (node (ref "C31") (pin "1") (pintype "passive"))
      (node (ref "C32") (pin "1") (pintype "passive"))
      (node (ref "C33") (pin "1") (pintype "passive"))
      (node (ref "C34") (pin "1") (pintype "passive"))
      (node (ref "C37") (pin "2") (pintype "passive"))
      (node (ref "C4") (pin "2") (pinfunction "+_2") (pintype "passive"))
      (node (ref "P1") (pin "2") (pinfunction "2_2") (pintype "passive"))
      (node (ref "P10") (pin "1") (pinfunction "1_1") (pintype "passive"))
      (node (ref "P11") (pin "3") (pinfunction "VCC_3") (pintype "passive"))
      (node (ref "P12") (pin "1") (pinfunction "1_1") (pintype "passive"))
      (node (ref "P14") (pin "4") (pinfunction "4_4") (pintype "passive"))
      (node (ref "P15") (pin "1") (pinfunction "1_1") (pintype "passive"))
      (node (ref "P16") (pin "1") (pinfunction "1_1") (pintype "passive"))
      (node (ref "P17") (pin "8") (pinfunction "5V_8") (pintype "passive"))
      (node (ref "P18") (pin "1") (pinfunction "1_1") (pintype "passive"))
      (node (ref "P18") (pin "3") (pinfunction "3_3") (pintype "passive"))
      (node (ref "P18") (pin "5") (pinfunction "5_5") (pintype "passive"))
      (node (ref "P20") (pin "1") (pinfunction "1_1") (pintype "passive"))
      (node (ref "P20") (pin "4") (pinfunction "4_4") (pintype "passive"))
      (node (ref "P21") (pin "1") (pinfunction "1_1") (pintype "passive"))
      (node (ref "P21") (pin "4") (pinfunction "4_4") (pintype "passive"))
      (node (ref "P24") (pin "2") (pinfunction "2_2") (pintype "passive"))
      (node (ref "P25") (pin "1") (pinfunction "SCL_1") (pintype "passive"))
      (node (ref "P3") (pin "2") (pinfunction "2_2") (pintype "passive"))
      (node (ref "P4") (pin "2") (pinfunction "2_2") (pintype "passive"))
      (node (ref "P5") (pin "2") (pinfunction "VIN_2") (pintype "passive"))
      (node (ref "P6") (pin "1") (pinfunction "1_1") (pintype "passive"))
      (node (ref "P7") (pin "1") (pinfunction "1_1") (pintype "passive"))
      (node (ref "P8") (pin "1") (pinfunction "1_1") (pintype "passive"))
      (node (ref "P9") (pin "1") (pinfunction "1_1") (pintype "passive"))
      (node (ref "R10") (pin "2") (pinfunction "2_2") (pintype "passive"))
      (node (ref "R3") (pin "2") (pinfunction "2_2") (pintype "passive"))
      (node (ref "R7") (pin "2") (pinfunction "2_2") (pintype "passive"))
      (node (ref "R8") (pin "2") (pinfunction "2_2") (pintype "passive"))
      (node (ref "U1") (pin "18") (pinfunction "VDD_18") (pintype "power_in"))
      (node (ref "U2") (pin "3") (pinfunction "VDD_3") (pintype "passive"))
    )
    (net (code "61") (name "AGND") (class "Default")
      (node (ref "C10") (pin "2") (pintype "passive"))
      (node (ref "C11") (pin "2") (pintype "passive"))
      (node (ref "C12") (pin "2") (pintype "passive"))
      (node (ref "C21") (pin "2") (pintype "passive"))
      (node (ref "C22") (pin "2") (pintype "passive"))
      (node (ref "C24") (pin "2") (pintype "passive"))
      (node (ref "C25") (pin "2") (pintype "passive"))
      (node (ref "C26") (pin "2") (pintype "passive"))
      (node (ref "C28") (pin "2") (pintype "passive"))
      (node (ref "C31") (pin "2") (pintype "passive"))
      (node (ref "C32") (pin "2") (pintype "passive"))
      (node (ref "C33") (pin "2") (pintype "passive"))
      (node (ref "C34") (pin "2") (pintype "passive"))
      (node (ref "C7") (pin "2") (pintype "passive"))
      (node (ref "C8") (pin "2") (pintype "passive"))
      (node (ref "C9") (pin "2") (pintype "passive"))
      (node (ref "P10") (pin "3") (pinfunction "3_3") (pintype "passive"))
      (node (ref "P12") (pin "3") (pinfunction "3_3") (pintype "passive"))
      (node (ref "P20") (pin "3") (pinfunction "3_3") (pintype "passive"))
      (node (ref "P20") (pin "6") (pinfunction "6_6") (pintype "passive"))
      (node (ref "P21") (pin "3") (pinfunction "3_3") (pintype "passive"))
      (node (ref "P21") (pin "6") (pinfunction "6_6") (pintype "passive"))
      (node (ref "P6") (pin "3") (pinfunction "3_3") (pintype "passive"))
      (node (ref "P7") (pin "3") (pinfunction "3_3") (pintype "passive"))
      (node (ref "P8") (pin "3") (pinfunction "3_3") (pintype "passive"))
      (node (ref "P9") (pin "3") (pinfunction "3_3") (pintype "passive"))
      (node (ref "R9") (pin "2") (pinfunction "2_2") (pintype "passive"))
    )
    (net (code "62") (name "GND") (class "Default")
      (node (ref "*") (pin "GND") (pinfunction "GND_GND") (pintype "passive"))
      (node (ref "C1") (pin "1") (pinfunction "-_1") (pintype "passive"))
      (node (ref "C13") (pin "2") (pinfunction "2_2") (pintype "passive"))
      (node (ref "C14") (pin "2") (pinfunction "2_2") (pintype "passive"))
      (node (ref "C15") (pin "2") (pinfunction "2_2") (pintype "passive"))
      (node (ref "C16") (pin "2") (pintype "passive"))
      (node (ref "C17") (pin "2") (pintype "passive"))
      (node (ref "C18") (pin "2") (pintype "passive"))
      (node (ref "C19") (pin "2") (pintype "passive"))
      (node (ref "C2") (pin "1") (pinfunction "-_1") (pintype "passive"))
      (node (ref "C20") (pin "1") (pintype "passive"))
      (node (ref "C23") (pin "2") (pintype "passive"))
      (node (ref "C27") (pin "1") (pintype "passive"))
      (node (ref "C29") (pin "2") (pintype "passive"))
      (node (ref "C3") (pin "1") (pinfunction "-_1") (pintype "passive"))
      (node (ref "C30") (pin "1") (pintype "passive"))
      (node (ref "C35") (pin "2") (pinfunction "2_2") (pintype "passive"))
      (node (ref "C36") (pin "2") (pinfunction "2_2") (pintype "passive"))
      (node (ref "C37") (pin "1") (pintype "passive"))
      (node (ref "C4") (pin "1") (pinfunction "-_1") (pintype "passive"))
      (node (ref "C5") (pin "1") (pinfunction "1_1") (pintype "passive"))
      (node (ref "C6") (pin "1") (pinfunction "1_1") (pintype "passive"))
      (node (ref "LED1") (pin "C") (pinfunction "C_C") (pintype "passive"))
      (node (ref "P1") (pin "3") (pinfunction "3_3") (pintype "passive"))
      (node (ref "P11") (pin "4") (pinfunction "GND_4") (pintype "passive"))
      (node (ref "P13") (pin "1") (pinfunction "-_1") (pintype "passive"))
      (node (ref "P14") (pin "2") (pinfunction "2_2") (pintype "passive"))
      (node (ref "P14") (pin "3") (pinfunction "3_3") (pintype "passive"))
      (node (ref "P15") (pin "2") (pinfunction "2_2") (pintype "passive"))
      (node (ref "P16") (pin "4") (pinfunction "4_4") (pintype "passive"))
      (node (ref "P17") (pin "6") (pinfunction "GND_6") (pintype "passive"))
      (node (ref "P19") (pin "2") (pinfunction "2_2") (pintype "passive"))
      (node (ref "P2") (pin "4") (pinfunction "4_4") (pintype "passive"))
      (node (ref "P23") (pin "1") (pinfunction "1_1") (pintype "passive"))
      (node (ref "P24") (pin "1") (pinfunction "1_1") (pintype "passive"))
      (node (ref "P25") (pin "2") (pinfunction "SDA_2") (pintype "passive"))
      (node (ref "P3") (pin "3") (pinfunction "3_3") (pintype "passive"))
      (node (ref "P4") (pin "3") (pinfunction "3_3") (pintype "passive"))
      (node (ref "P5") (pin "1") (pinfunction "GND_1") (pintype "passive"))
      (node (ref "R12") (pin "2") (pinfunction "2_2") (pintype "passive"))
      (node (ref "R14") (pin "2") (pinfunction "2_2") (pintype "passive"))
      (node (ref "R16") (pin "2") (pinfunction "2_2") (pintype "passive"))
      (node (ref "R19") (pin "1") (pinfunction "1_1") (pintype "passive"))
      (node (ref "R2") (pin "1") (pinfunction "1_1") (pintype "passive"))
      (node (ref "R4") (pin "1") (pinfunction "1_1") (pintype "passive"))
      (node (ref "R9") (pin "1") (pinfunction "1_1") (pintype "passive"))
      (node (ref "U1") (pin "9") (pinfunction "VSS_9") (pintype "power_in"))
      (node (ref "U2") (pin "2") (pinfunction "VSS_2") (pintype "passive"))
    )
    (net (code "63") (name "Net-(C5-Pad2)") (class "Default")
      (node (ref "C5") (pin "2") (pinfunction "2_2") (pintype "passive"))
      (node (ref "R5") (pin "1") (pinfunction "1_1") (pintype "passive"))
    )
    (net (code "64") (name "Net-(C6-Pad2)") (class "Default")
      (node (ref "C6") (pin "2") (pinfunction "2_2") (pintype "passive"))
      (node (ref "R6") (pin "1") (pinfunction "1_1") (pintype "passive"))
    )
    (net (code "65") (name "Net-(D1-K)") (class "Default")
      (node (ref "D1") (pin "2") (pinfunction "K_2") (pintype "passive"))
      (node (ref "F1") (pin "1") (pinfunction "1_1") (pintype "passive"))
    )
    (net (code "66") (name "Net-(LED1-PadA)") (class "Default")
      (node (ref "LED1") (pin "A") (pinfunction "A_A") (pintype "passive"))
      (node (ref "R3") (pin "1") (pinfunction "1_1") (pintype "passive"))
    )
    (net (code "67") (name "Net-(P2-Pad2)") (class "Default")
      (node (ref "P2") (pin "2") (pinfunction "2_2") (pintype "passive"))
      (node (ref "R1") (pin "2") (pinfunction "2_2") (pintype "passive"))
    )
    (net (code "68") (name "Net-(P18-Pad2)") (class "Default")
      (node (ref "P18") (pin "2") (pinfunction "2_2") (pintype "passive"))
      (node (ref "R11") (pin "1") (pinfunction "1_1") (pintype "passive"))
      (node (ref "R12") (pin "1") (pinfunction "1_1") (pintype "passive"))
    )
    (net (code "69") (name "Net-(P18-Pad4)") (class "Default")
      (node (ref "P18") (pin "4") (pinfunction "4_4") (pintype "passive"))
      (node (ref "R13") (pin "1") (pinfunction "1_1") (pintype "passive"))
      (node (ref "R14") (pin "1") (pinfunction "1_1") (pintype "passive"))
    )
    (net (code "70") (name "Net-(P18-Pad6)") (class "Default")
      (node (ref "P18") (pin "6") (pinfunction "6_6") (pintype "passive"))
      (node (ref "R15") (pin "1") (pinfunction "1_1") (pintype "passive"))
      (node (ref "R16") (pin "1") (pinfunction "1_1") (pintype "passive"))
    )
    (net (code "71") (name "Net-(P19-Pad1)") (class "Default")
      (node (ref "P19") (pin "1") (pinfunction "1_1") (pintype "passive"))
      (node (ref "R17") (pin "1") (pinfunction "1_1") (pintype "passive"))
    )
    (net (code "72") (name "Net-(Q2-D)") (class "Default")
      (node (ref "P23") (pin "2") (pinfunction "2_2") (pintype "passive"))
      (node (ref "Q2") (pin "3") (pinfunction "D_3") (pintype "passive"))
    )
    (net (code "73") (name "Net-(U1A-OSC1)") (class "Default")
      (node (ref "C35") (pin "1") (pinfunction "1_1") (pintype "passive"))
      (node (ref "Q1") (pin "2") (pinfunction "2_2") (pintype "passive"))
      (node (ref "U1") (pin "8") (pinfunction "OSC1_8") (pintype "passive"))
    )
    (net (code "74") (name "Net-(U1A-OSC2)") (class "Default")
      (node (ref "C36") (pin "1") (pinfunction "1_1") (pintype "passive"))
      (node (ref "Q1") (pin "1") (pinfunction "1_1") (pintype "passive"))
      (node (ref "U1") (pin "7") (pinfunction "OSC2_7") (pintype "output"))
    )
    (net (code "75") (name "Net-(U2-RS)") (class "Default")
      (node (ref "R4") (pin "2") (pinfunction "2_2") (pintype "passive"))
      (node (ref "U2") (pin "8") (pinfunction "RS_8") (pintype "passive"))
    )
    (net (code "76") (name "VCC") (class "Default")
      (node (ref "C1") (pin "2") (pinfunction "+_2") (pintype "passive"))
      (node (ref "C2") (pin "2") (pinfunction "+_2") (pintype "passive"))
      (node (ref "F1") (pin "2") (pinfunction "2_2") (pintype "passive"))
      (node (ref "P14") (pin "1") (pinfunction "1_1") (pintype "passive"))
      (node (ref "Q2") (pin "2") (pinfunction "S_2") (pintype "passive"))
    )
    (net (code "77") (name "unconnected-(*-0(RX0)-PadRX0)") (class "Default")
      (node (ref "*") (pin "RX0") (pinfunction "0(RX0)_RX0") (pintype "passive"))
    )
    (net (code "78") (name "unconnected-(*-1(TX0)-PadTX0)") (class "Default")
      (node (ref "*") (pin "TX0") (pinfunction "1(TX0)_TX0") (pintype "passive"))
    )
    (net (code "79") (name "unconnected-(*-14(TX3)-PadTX3)") (class "Default")
      (node (ref "*") (pin "TX3") (pinfunction "14(TX3)_TX3") (pintype "passive"))
    )
    (net (code "80") (name "unconnected-(*-15(RX3)-PadRX3)") (class "Default")
      (node (ref "*") (pin "RX3") (pinfunction "15(RX3)_RX3") (pintype "passive"))
    )
    (net (code "81") (name "unconnected-(*-Pad3)") (class "Default")
      (node (ref "*") (pin "3") (pinfunction "3_3") (pintype "passive"))
    )
    (net (code "82") (name "unconnected-(*-Pad4)") (class "Default")
      (node (ref "*") (pin "4") (pinfunction "4_4") (pintype "passive"))
    )
    (net (code "83") (name "unconnected-(*-Pad6)") (class "Default")
      (node (ref "*") (pin "6") (pinfunction "6_6") (pintype "passive"))
    )
    (net (code "84") (name "unconnected-(*-Pad7)") (class "Default")
      (node (ref "*") (pin "7") (pinfunction "7_7") (pintype "passive"))
    )
    (net (code "85") (name "unconnected-(*-Pad8)") (class "Default")
      (node (ref "*") (pin "8") (pinfunction "8_8") (pintype "passive"))
    )
    (net (code "86") (name "unconnected-(*-Pad9)") (class "Default")
      (node (ref "*") (pin "9") (pinfunction "9_9") (pintype "passive"))
    )
    (net (code "87") (name "unconnected-(*-Pad10)") (class "Default")
      (node (ref "*") (pin "10") (pinfunction "10_10") (pintype "passive"))
    )
    (net (code "88") (name "unconnected-(*-Pad11)") (class "Default")
      (node (ref "*") (pin "11") (pinfunction "11_11") (pintype "passive"))
    )
    (net (code "89") (name "unconnected-(*-Pad12)") (class "Default")
      (node (ref "*") (pin "12") (pinfunction "12_12") (pintype "passive"))
    )
    (net (code "90") (name "unconnected-(*-Pad13)") (class "Default")
      (node (ref "*") (pin "13") (pinfunction "13_13") (pintype "passive"))
    )
    (net (code "91") (name "unconnected-(*-Pad22)") (class "Default")
      (node (ref "*") (pin "22") (pinfunction "22_22") (pintype "passive"))
    )
    (net (code "92") (name "unconnected-(*-PadA0)") (class "Default")
      (node (ref "*") (pin "A0") (pinfunction "A0_A0") (pintype "passive"))
    )
    (net (code "93") (name "unconnected-(*-PadA1)") (class "Default")
      (node (ref "*") (pin "A1") (pinfunction "A1_A1") (pintype "passive"))
    )
    (net (code "94") (name "unconnected-(*-PadA14)") (class "Default")
      (node (ref "*") (pin "A14") (pinfunction "A14_A14") (pintype "passive"))
    )
    (net (code "95") (name "unconnected-(*-PadA15)") (class "Default")
      (node (ref "*") (pin "A15") (pinfunction "A15_A15") (pintype "passive"))
    )
    (net (code "96") (name "unconnected-(*-PadAREF)") (class "Default")
      (node (ref "*") (pin "AREF") (pinfunction "AREF_AREF") (pintype "passive"))
    )
    (net (code "97") (name "unconnected-(*-PadIOREF)") (class "Default")
      (node (ref "*") (pin "IOREF") (pinfunction "IOREF_IOREF") (pintype "passive"))
    )
    (net (code "98") (name "unconnected-(*-PadVIN)") (class "Default")
      (node (ref "*") (pin "VIN") (pinfunction "VIN_VIN") (pintype "passive"))
    )
    (net (code "99") (name "unconnected-(P5-CD-Pad3)") (class "Default")
      (node (ref "P5") (pin "3") (pinfunction "CD_3") (pintype "passive"))
    )
    (net (code "100") (name "unconnected-(P17-3V-Pad7)") (class "Default")
      (node (ref "P17") (pin "7") (pinfunction "3V_7") (pintype "passive"))
    )
    (net (code "101") (name "unconnected-(U1A-CLKOUT-Pad3)") (class "Default")
      (node (ref "U1") (pin "3") (pinfunction "CLKOUT_3") (pintype "output"))
    )
    (net (code "102") (name "unconnected-(U1A-RX0BF-Pad11)") (class "Default")
      (node (ref "U1") (pin "11") (pinfunction "RX0BF_11") (pintype "output"))
    )
    (net (code "103") (name "unconnected-(U1A-RX1BF-Pad10)") (class "Default")
      (node (ref "U1") (pin "10") (pinfunction "RX1BF_10") (pintype "output"))
    )
    (net (code "104") (name "unconnected-(U1A-TX0RTS-Pad4)") (class "Default")
      (node (ref "U1") (pin "4") (pinfunction "TX0RTS_4") (pintype "passive"))
    )
    (net (code "105") (name "unconnected-(U1A-TX1RTS-Pad5)") (class "Default")
      (node (ref "U1") (pin "5") (pinfunction "TX1RTS_5") (pintype "passive"))
    )
    (net (code "106") (name "unconnected-(U1A-TX2RTS-Pad6)") (class "Default")
      (node (ref "U1") (pin "6") (pinfunction "TX2RTS_6") (pintype "passive"))
    )
    (net (code "107") (name "unconnected-(U2-VREF-Pad5)") (class "Default")
      (node (ref "U2") (pin "5") (pinfunction "VREF_5") (pintype "passive"))
    )
  )
)
